# Sheet1.net
KiCad netlist of a schematic drawn in Altium Designer
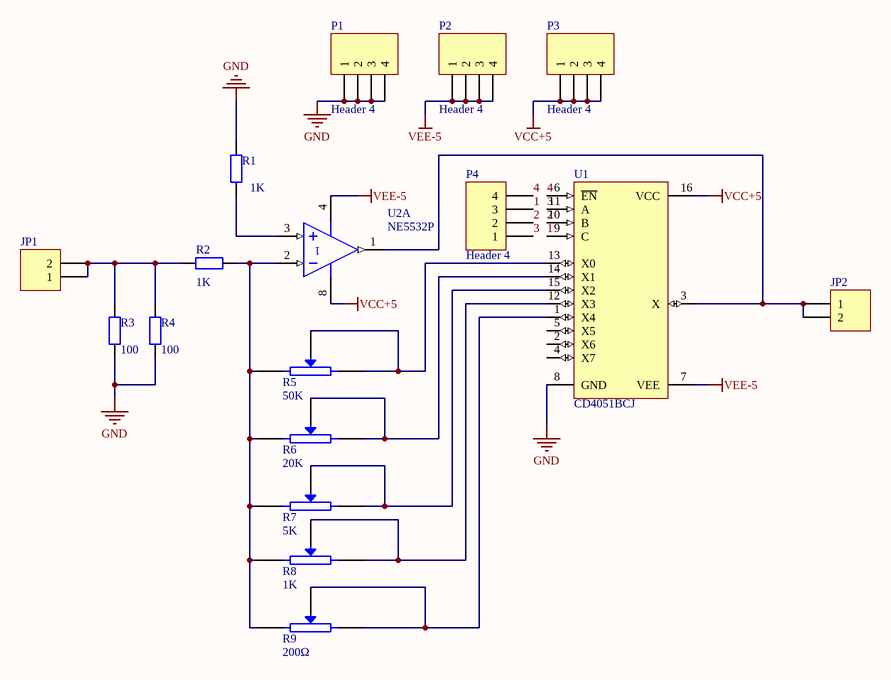
[diagram p0: Sheet1.SchDoc]

(export (version "E")
  (design (tool "Eeschema 10.0.6"))
  (components
    (comp (ref "JP1")
      (value "Header 2")
      (footprint "HDR1X2")
      (description "Header, 2-Pin")
      (fields (field (name "PUBLISHER") "Altium Limited"))
      (libsource (lib "电位器") (part "Header 2"))
    )
    (comp (ref "JP2")
      (value "Header 2")
      (footprint "HDR1X2")
      (description "Header, 2-Pin")
      (fields (field (name "PUBLISHER") "Altium Limited"))
      (libsource (lib "") (part "Header 2_1"))
    )
    (comp (ref "P1")
      (value "Header 4")
      (footprint "HDR1X4")
      (description "Header, 4-Pin")
      (fields (field (name "PUBLISHER") "Altium Limited"))
      (libsource (lib "") (part "Header 4_1"))
    )
    (comp (ref "P2")
      (value "Header 4")
      (footprint "HDR1X4")
      (description "Header, 4-Pin")
      (fields (field (name "PUBLISHER") "Altium Limited"))
      (libsource (lib "") (part "Header 4_1"))
    )
    (comp (ref "P3")
      (value "Header 4")
      (footprint "HDR1X4")
      (description "Header, 4-Pin")
      (fields (field (name "PUBLISHER") "Altium Limited"))
      (libsource (lib "") (part "Header 4_1"))
    )
    (comp (ref "P4")
      (value "Header 4")
      (footprint "HDR1X4")
      (description "Header, 4-Pin")
      (fields (field (name "PUBLISHER") "Altium Limited"))
      (libsource (lib "Miscellaneous Connectors") (part "Header 4"))
    )
    (comp (ref "R1")
      (value "1K")
      (footprint "0805")
      (description "Resistor")
      (fields (field (name "Comment") "Res2") (field (name "PUBLISHER") "Altium Limited"))
      (libsource (lib "") (part "Res2_1"))
    )
    (comp (ref "R2")
      (value "1K")
      (footprint "0805")
      (description "Resistor")
      (fields (field (name "Comment") "Res2") (field (name "PUBLISHER") "Altium Limited"))
      (libsource (lib "Miscellaneous Devices") (part "Res2"))
    )
    (comp (ref "R3")
      (value "100")
      (footprint "0805")
      (description "Resistor")
      (fields (field (name "Comment") "Res2") (field (name "PUBLISHER") "Altium Limited"))
      (libsource (lib "") (part "Res2_1"))
    )
    (comp (ref "R4")
      (value "100")
      (footprint "0805")
      (description "Resistor")
      (fields (field (name "Comment") "Res2") (field (name "PUBLISHER") "Altium Limited"))
      (libsource (lib "") (part "Res2_1"))
    )
    (comp (ref "R5")
      (value "50K")
      (footprint "VR5")
      (description "Potentiometer")
      (libsource (lib "*") (part "POT2"))
    )
    (comp (ref "R6")
      (value "20K")
      (footprint "VR5")
      (description "Potentiometer")
      (libsource (lib "*") (part "POT2"))
    )
    (comp (ref "R7")
      (value "5K")
      (footprint "VR5")
      (description "Potentiometer")
      (libsource (lib "*") (part "POT2"))
    )
    (comp (ref "R8")
      (value "1K")
      (footprint "VR5")
      (description "Potentiometer")
      (libsource (lib "*") (part "POT2"))
    )
    (comp (ref "R9")
      (value "200Ω")
      (footprint "VR5")
      (description "Potentiometer")
      (libsource (lib "*") (part "POT2"))
    )
    (comp (ref "U1")
      (value "CD4051BCJ")
      (footprint "J16A")
      (description "8-Channel Analog Multiplexer/Demultiplexer")
      (fields (field (name "PUBLISHER") "Altium Limited"))
      (libsource (lib "NSC Logic Multiplexer") (part "CD4051BCJ"))
    )
    (comp (ref "U2")
      (value "NE5532P")
      (footprint "P008")
      (description "Dual Low-Noise Operational Amplifier")
      (fields (field (name "PUBLISHER") "Altium Limited"))
      (libsource (lib "TI Operational Amplifier") (part "NE5532P"))
    )
  )
  (nets
    (net (code "1") (name "/1") (class "Default")
      (node (ref "P4") (pin "3") (pinfunction "3_3") (pintype "passive"))
      (node (ref "U1") (pin "9") (pinfunction "C_9") (pintype "input"))
    )
    (net (code "2") (name "/2") (class "Default")
      (node (ref "P4") (pin "2") (pinfunction "2_2") (pintype "passive"))
      (node (ref "U1") (pin "10") (pinfunction "B_10") (pintype "input"))
    )
    (net (code "3") (name "/3") (class "Default")
      (node (ref "P4") (pin "1") (pinfunction "1_1") (pintype "passive"))
      (node (ref "U1") (pin "11") (pinfunction "A_11") (pintype "input"))
    )
    (net (code "4") (name "/4") (class "Default")
      (node (ref "P4") (pin "4") (pinfunction "4_4") (pintype "passive"))
      (node (ref "U1") (pin "6") (pinfunction "~{EN}_6") (pintype "input"))
    )
    (net (code "5") (name "GND") (class "Default")
      (node (ref "P1") (pin "1") (pinfunction "1_1") (pintype "passive"))
      (node (ref "P1") (pin "2") (pinfunction "2_2") (pintype "passive"))
      (node (ref "P1") (pin "3") (pinfunction "3_3") (pintype "passive"))
      (node (ref "P1") (pin "4") (pinfunction "4_4") (pintype "passive"))
      (node (ref "R1") (pin "2") (pinfunction "2_2") (pintype "passive"))
      (node (ref "R3") (pin "1") (pinfunction "1_1") (pintype "passive"))
      (node (ref "R4") (pin "1") (pinfunction "1_1") (pintype "passive"))
      (node (ref "U1") (pin "8") (pinfunction "GND_8") (pintype "power_in"))
    )
    (net (code "6") (name "Net-(JP1-Pad1)") (class "Default")
      (node (ref "JP1") (pin "1") (pinfunction "1_1") (pintype "passive"))
      (node (ref "JP1") (pin "2") (pinfunction "2_2") (pintype "passive"))
      (node (ref "R2") (pin "1") (pinfunction "1_1") (pintype "passive"))
      (node (ref "R3") (pin "2") (pinfunction "2_2") (pintype "passive"))
      (node (ref "R4") (pin "2") (pinfunction "2_2") (pintype "passive"))
    )
    (net (code "7") (name "Net-(R5-W)") (class "Default")
      (node (ref "R5") (pin "2") (pinfunction "2_2") (pintype "passive"))
      (node (ref "R5") (pin "3") (pinfunction "W_3") (pintype "passive"))
      (node (ref "U1") (pin "13") (pinfunction "X0_13") (pintype "bidirectional"))
    )
    (net (code "8") (name "Net-(R6-W)") (class "Default")
      (node (ref "R6") (pin "2") (pinfunction "2_2") (pintype "passive"))
      (node (ref "R6") (pin "3") (pinfunction "W_3") (pintype "passive"))
      (node (ref "U1") (pin "14") (pinfunction "X1_14") (pintype "bidirectional"))
    )
    (net (code "9") (name "Net-(R7-W)") (class "Default")
      (node (ref "R7") (pin "2") (pinfunction "2_2") (pintype "passive"))
      (node (ref "R7") (pin "3") (pinfunction "W_3") (pintype "passive"))
      (node (ref "U1") (pin "15") (pinfunction "X2_15") (pintype "bidirectional"))
    )
    (net (code "10") (name "Net-(R8-W)") (class "Default")
      (node (ref "R8") (pin "2") (pinfunction "2_2") (pintype "passive"))
      (node (ref "R8") (pin "3") (pinfunction "W_3") (pintype "passive"))
      (node (ref "U1") (pin "12") (pinfunction "X3_12") (pintype "bidirectional"))
    )
    (net (code "11") (name "Net-(R9-W)") (class "Default")
      (node (ref "R9") (pin "2") (pinfunction "2_2") (pintype "passive"))
      (node (ref "R9") (pin "3") (pinfunction "W_3") (pintype "passive"))
      (node (ref "U1") (pin "1") (pinfunction "X4_1") (pintype "bidirectional"))
    )
    (net (code "12") (name "Net-(U1-X)") (class "Default")
      (node (ref "JP2") (pin "1") (pinfunction "1_1") (pintype "passive"))
      (node (ref "JP2") (pin "2") (pinfunction "2_2") (pintype "passive"))
      (node (ref "U1") (pin "3") (pinfunction "X_3") (pintype "bidirectional"))
      (node (ref "U2") (pin "1") (pinfunction "OUT_1") (pintype "output"))
    )
    (net (code "13") (name "Net-(U2A-IN+)") (class "Default")
      (node (ref "R1") (pin "1") (pinfunction "1_1") (pintype "passive"))
      (node (ref "U2") (pin "3") (pinfunction "IN+_3") (pintype "input"))
    )
    (net (code "14") (name "Net-(U2A-IN-)") (class "Default")
      (node (ref "R2") (pin "2") (pinfunction "2_2") (pintype "passive"))
      (node (ref "R5") (pin "1") (pinfunction "1_1") (pintype "passive"))
      (node (ref "R6") (pin "1") (pinfunction "1_1") (pintype "passive"))
      (node (ref "R7") (pin "1") (pinfunction "1_1") (pintype "passive"))
      (node (ref "R8") (pin "1") (pinfunction "1_1") (pintype "passive"))
      (node (ref "R9") (pin "1") (pinfunction "1_1") (pintype "passive"))
      (node (ref "U2") (pin "2") (pinfunction "IN-_2") (pintype "input"))
    )
    (net (code "15") (name "VCC+5") (class "Default")
      (node (ref "P3") (pin "1") (pinfunction "1_1") (pintype "passive"))
      (node (ref "P3") (pin "2") (pinfunction "2_2") (pintype "passive"))
      (node (ref "P3") (pin "3") (pinfunction "3_3") (pintype "passive"))
      (node (ref "P3") (pin "4") (pinfunction "4_4") (pintype "passive"))
      (node (ref "U1") (pin "16") (pinfunction "VCC_16") (pintype "power_in"))
      (node (ref "U2") (pin "8") (pinfunction "V+_8") (pintype "power_in"))
    )
    (net (code "16") (name "VEE-5") (class "Default")
      (node (ref "P2") (pin "1") (pinfunction "1_1") (pintype "passive"))
      (node (ref "P2") (pin "2") (pinfunction "2_2") (pintype "passive"))
      (node (ref "P2") (pin "3") (pinfunction "3_3") (pintype "passive"))
      (node (ref "P2") (pin "4") (pinfunction "4_4") (pintype "passive"))
      (node (ref "U1") (pin "7") (pinfunction "VEE_7") (pintype "power_in"))
      (node (ref "U2") (pin "4") (pinfunction "V-_4") (pintype "power_in"))
    )
    (net (code "17") (name "unconnected-(U1-X5-Pad5)") (class "Default")
      (node (ref "U1") (pin "5") (pinfunction "X5_5") (pintype "bidirectional"))
    )
    (net (code "18") (name "unconnected-(U1-X6-Pad2)") (class "Default")
      (node (ref "U1") (pin "2") (pinfunction "X6_2") (pintype "bidirectional"))
    )
    (net (code "19") (name "unconnected-(U1-X7-Pad4)") (class "Default")
      (node (ref "U1") (pin "4") (pinfunction "X7_4") (pintype "bidirectional"))
    )
  )
)
